# GTwoShield4PATCH2.net
KiCad netlist of a schematic drawn in EAGLE
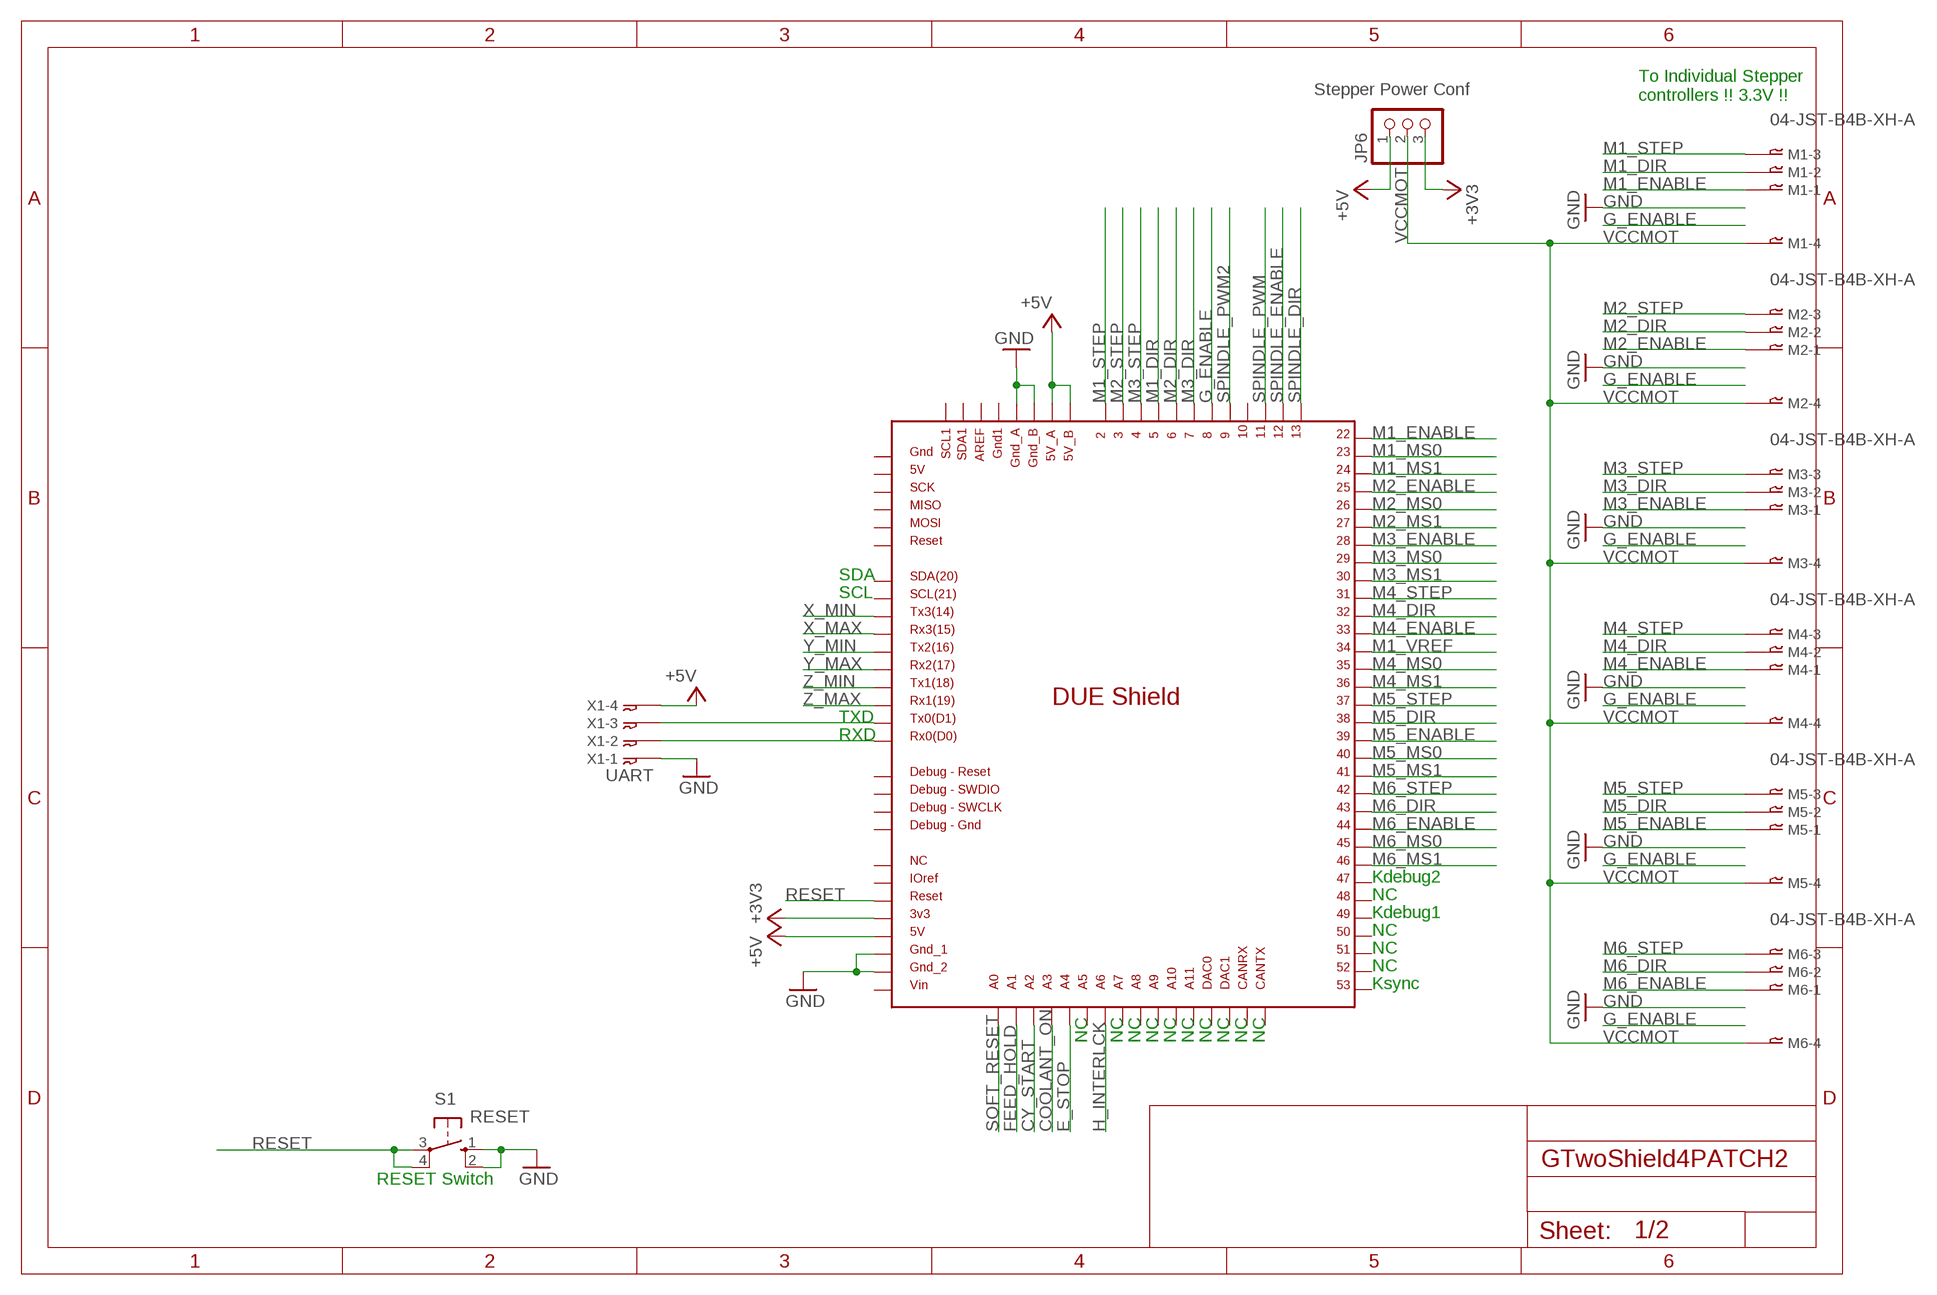
[diagram p0: schematic, sheet 1]
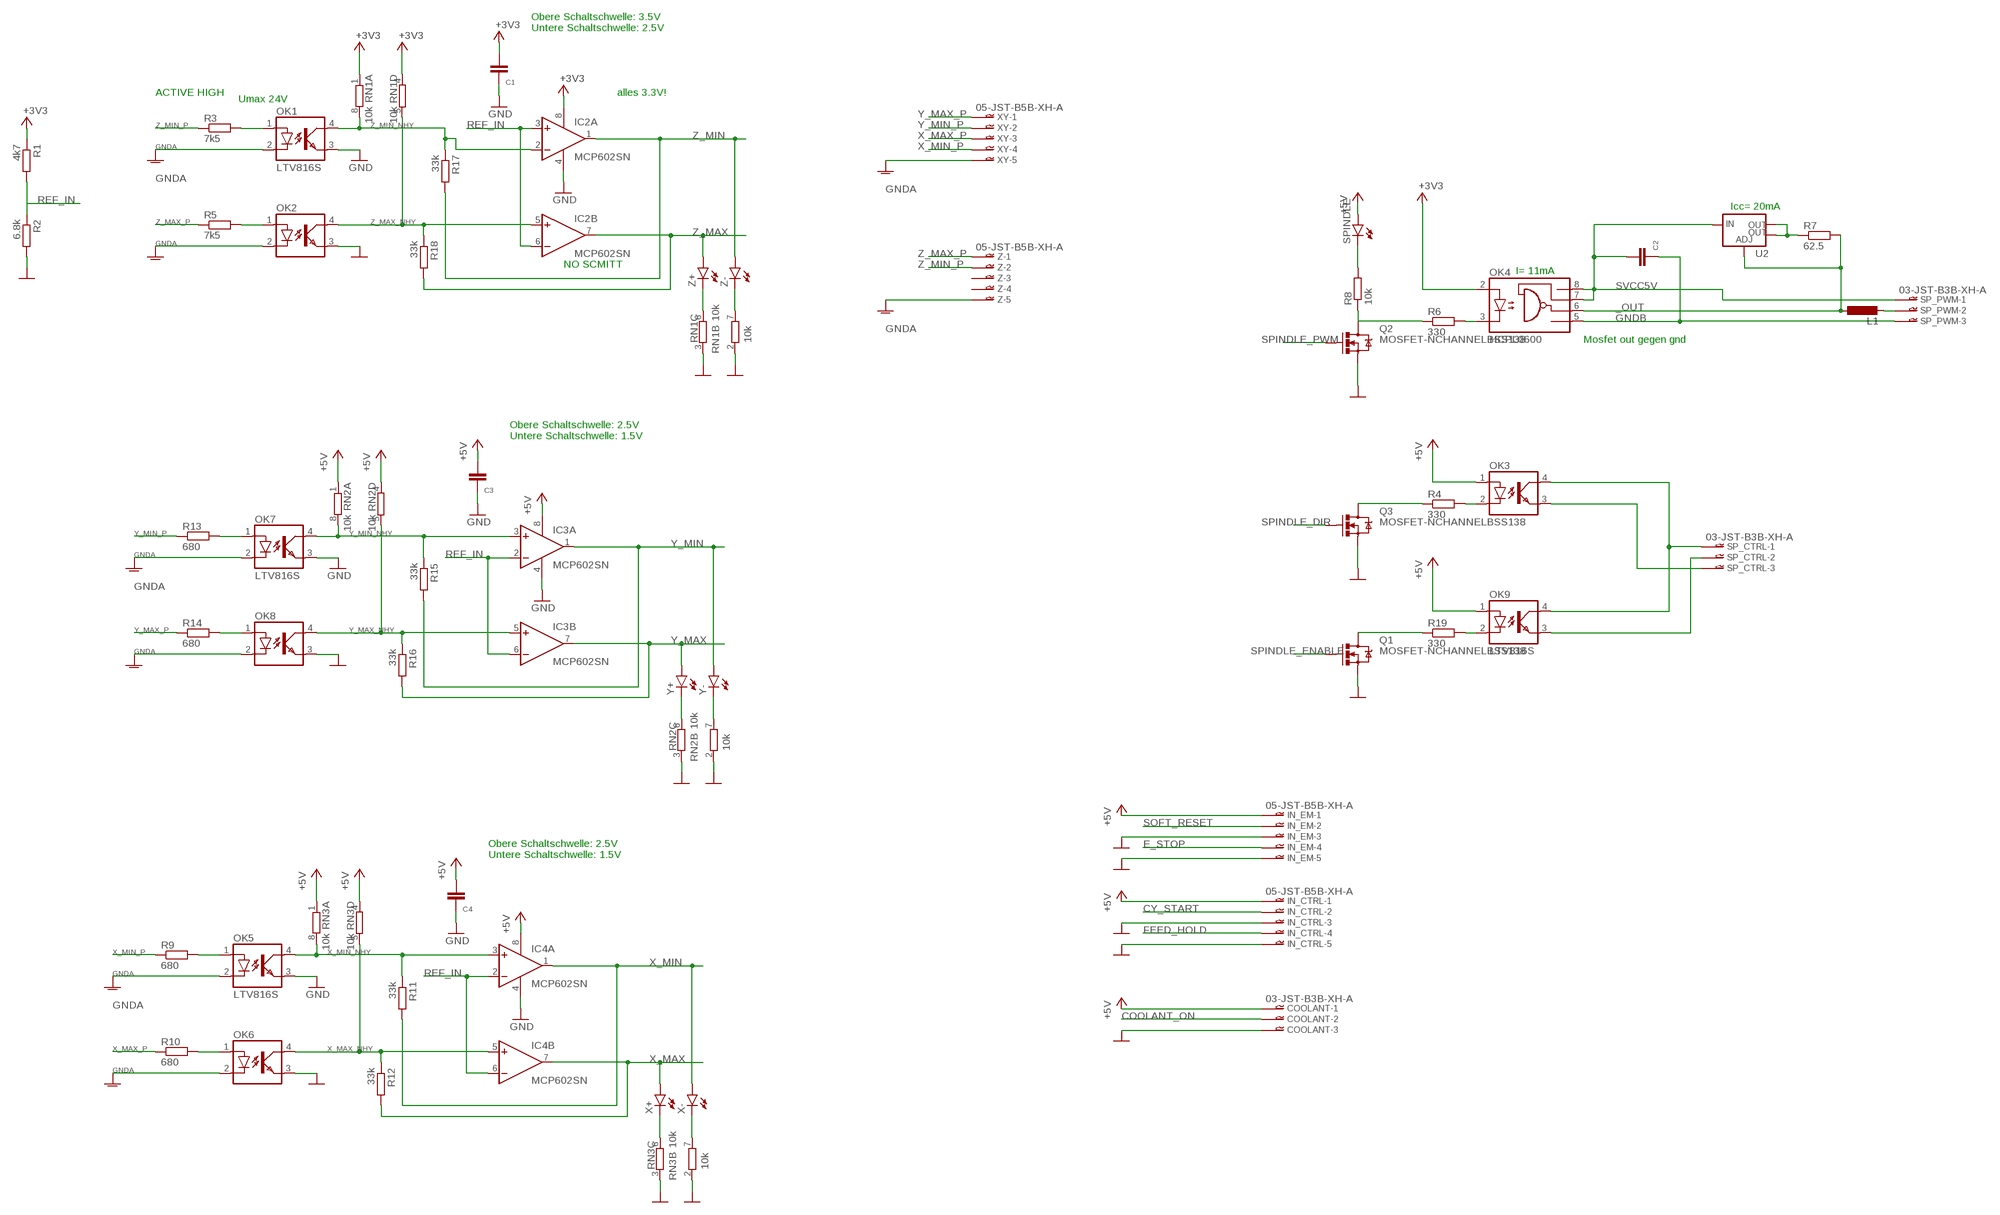
[diagram p1: schematic, sheet 2]

(export (version "E")
  (design (tool "Eeschema 10.0.6"))
  (components
    (comp (ref "C1")
      (value "100nf")
      (footprint "eagle-import:C0603K")
      (libsource (lib "eagle-import") (part "C-EUC0603K"))
    )
    (comp (ref "C2")
      (value "100nf")
      (footprint "eagle-import:C0603K")
      (libsource (lib "eagle-import") (part "C-EUC0603K"))
    )
    (comp (ref "C3")
      (value "100nf")
      (footprint "eagle-import:C0603K")
      (libsource (lib "eagle-import") (part "C-EUC0603K"))
    )
    (comp (ref "C4")
      (value "100nf")
      (footprint "eagle-import:C0603K")
      (libsource (lib "eagle-import") (part "C-EUC0603K"))
    )
    (comp (ref "COOLANT")
      (value "03-JST-B3B-XH-A")
      (footprint "eagle-import:B3B-XH")
      (libsource (lib "eagle-import") (part "03-JST-B3B-XH-A"))
    )
    (comp (ref "IC2")
      (value "MCP602SN")
      (footprint "eagle-import:SO08")
      (libsource (lib "eagle-import") (part "MCP602SN"))
    )
    (comp (ref "IC3")
      (value "MCP602SN")
      (footprint "eagle-import:SO08")
      (libsource (lib "eagle-import") (part "MCP602SN"))
    )
    (comp (ref "IC4")
      (value "MCP602SN")
      (footprint "eagle-import:SO08")
      (libsource (lib "eagle-import") (part "MCP602SN"))
    )
    (comp (ref "IN_CTRL")
      (value "05-JST-B5B-XH-A")
      (footprint "eagle-import:B5B-XH")
      (libsource (lib "eagle-import") (part "05-JST-B5B-XH-A"))
    )
    (comp (ref "IN_EM")
      (value "05-JST-B5B-XH-A")
      (footprint "eagle-import:B5B-XH")
      (libsource (lib "eagle-import") (part "05-JST-B5B-XH-A"))
    )
    (comp (ref "L1")
      (value "L-EU0207/10")
      (footprint "eagle-import:0207_10")
      (libsource (lib "eagle-import") (part "L-EU0207/10"))
    )
    (comp (ref "OK1")
      (value "LTV816S")
      (footprint "eagle-import:DIL4-SMD")
      (fields (field (name "SPICEPREFIX") "O"))
      (libsource (lib "eagle-import") (part "LTV816S"))
    )
    (comp (ref "OK2")
      (value "LTV816S")
      (footprint "eagle-import:DIL4-SMD")
      (fields (field (name "SPICEPREFIX") "O"))
      (libsource (lib "eagle-import") (part "LTV816S"))
    )
    (comp (ref "OK3")
      (value "LTV816S")
      (footprint "eagle-import:DIL4-SMD")
      (fields (field (name "SPICEPREFIX") "O"))
      (libsource (lib "eagle-import") (part "LTV816S"))
    )
    (comp (ref "OK4")
      (value "HCPL0600")
      (footprint "eagle-import:SOIC08")
      (fields (field (name "MF") "AGILENT TECHNOLOGIES") (field (name "MPN") "HCPL-0600-000E"))
      (libsource (lib "eagle-import") (part "HCPL0600"))
    )
    (comp (ref "OK5")
      (value "LTV816S")
      (footprint "eagle-import:DIL4-SMD")
      (fields (field (name "SPICEPREFIX") "O"))
      (libsource (lib "eagle-import") (part "LTV816S"))
    )
    (comp (ref "OK6")
      (value "LTV816S")
      (footprint "eagle-import:DIL4-SMD")
      (fields (field (name "SPICEPREFIX") "O"))
      (libsource (lib "eagle-import") (part "LTV816S"))
    )
    (comp (ref "OK7")
      (value "LTV816S")
      (footprint "eagle-import:DIL4-SMD")
      (fields (field (name "SPICEPREFIX") "O"))
      (libsource (lib "eagle-import") (part "LTV816S"))
    )
    (comp (ref "OK8")
      (value "LTV816S")
      (footprint "eagle-import:DIL4-SMD")
      (fields (field (name "SPICEPREFIX") "O"))
      (libsource (lib "eagle-import") (part "LTV816S"))
    )
    (comp (ref "OK9")
      (value "LTV816S")
      (footprint "eagle-import:DIL4-SMD")
      (fields (field (name "SPICEPREFIX") "O"))
      (libsource (lib "eagle-import") (part "LTV816S"))
    )
    (comp (ref "Q1")
      (value "MOSFET-NCHANNELBSS138")
      (footprint "eagle-import:SOT23")
      (libsource (lib "eagle-import") (part "MOSFET-NCHANNELBSS138"))
    )
    (comp (ref "Q2")
      (value "MOSFET-NCHANNELBSS138")
      (footprint "eagle-import:SOT23")
      (libsource (lib "eagle-import") (part "MOSFET-NCHANNELBSS138"))
    )
    (comp (ref "Q3")
      (value "MOSFET-NCHANNELBSS138")
      (footprint "eagle-import:SOT23")
      (libsource (lib "eagle-import") (part "MOSFET-NCHANNELBSS138"))
    )
    (comp (ref "R1")
      (value "4k7")
      (footprint "eagle-import:R0805")
      (libsource (lib "eagle-import") (part "R-EU_R0805"))
    )
    (comp (ref "R2")
      (value "6.8k")
      (footprint "eagle-import:R0805")
      (libsource (lib "eagle-import") (part "R-EU_R0805"))
    )
    (comp (ref "R3")
      (value "7k5")
      (footprint "eagle-import:R0805")
      (fields (field (name "SPICEPREFIX") "R"))
      (libsource (lib "eagle-import") (part "resistor_348_R-EU_R0805"))
    )
    (comp (ref "R4")
      (value "330")
      (footprint "eagle-import:R0805")
      (fields (field (name "SPICEPREFIX") "R"))
      (libsource (lib "eagle-import") (part "resistor_348_R-EU_R0805"))
    )
    (comp (ref "R5")
      (value "7k5")
      (footprint "eagle-import:R0805")
      (fields (field (name "SPICEPREFIX") "R"))
      (libsource (lib "eagle-import") (part "resistor_348_R-EU_R0805"))
    )
    (comp (ref "R6")
      (value "330")
      (footprint "eagle-import:R0805")
      (fields (field (name "SPICEPREFIX") "R"))
      (libsource (lib "eagle-import") (part "resistor_348_R-EU_R0805"))
    )
    (comp (ref "R7")
      (value "62.5")
      (footprint "eagle-import:R0805")
      (fields (field (name "SPICEPREFIX") "R"))
      (libsource (lib "eagle-import") (part "resistor_348_R-EU_R0805"))
    )
    (comp (ref "R8")
      (value "10k")
      (footprint "eagle-import:R0805")
      (fields (field (name "SPICEPREFIX") "R"))
      (libsource (lib "eagle-import") (part "resistor_348_R-EU_R0805"))
    )
    (comp (ref "R9")
      (value "680")
      (footprint "eagle-import:R0805")
      (fields (field (name "SPICEPREFIX") "R"))
      (libsource (lib "eagle-import") (part "resistor_348_R-EU_R0805"))
    )
    (comp (ref "R10")
      (value "680")
      (footprint "eagle-import:R0805")
      (fields (field (name "SPICEPREFIX") "R"))
      (libsource (lib "eagle-import") (part "resistor_348_R-EU_R0805"))
    )
    (comp (ref "R11")
      (value "33k")
      (footprint "eagle-import:R0805")
      (libsource (lib "eagle-import") (part "R-EU_R0805"))
    )
    (comp (ref "R12")
      (value "33k")
      (footprint "eagle-import:R0805")
      (libsource (lib "eagle-import") (part "R-EU_R0805"))
    )
    (comp (ref "R13")
      (value "680")
      (footprint "eagle-import:R0805")
      (fields (field (name "SPICEPREFIX") "R"))
      (libsource (lib "eagle-import") (part "resistor_348_R-EU_R0805"))
    )
    (comp (ref "R14")
      (value "680")
      (footprint "eagle-import:R0805")
      (fields (field (name "SPICEPREFIX") "R"))
      (libsource (lib "eagle-import") (part "resistor_348_R-EU_R0805"))
    )
    (comp (ref "R15")
      (value "33k")
      (footprint "eagle-import:R0805")
      (libsource (lib "eagle-import") (part "R-EU_R0805"))
    )
    (comp (ref "R16")
      (value "33k")
      (footprint "eagle-import:R0805")
      (libsource (lib "eagle-import") (part "R-EU_R0805"))
    )
    (comp (ref "R17")
      (value "33k")
      (footprint "eagle-import:R0805")
      (libsource (lib "eagle-import") (part "R-EU_R0805"))
    )
    (comp (ref "R18")
      (value "33k")
      (footprint "eagle-import:R0805")
      (libsource (lib "eagle-import") (part "R-EU_R0805"))
    )
    (comp (ref "R19")
      (value "330")
      (footprint "eagle-import:R0805")
      (fields (field (name "SPICEPREFIX") "R"))
      (libsource (lib "eagle-import") (part "resistor_348_R-EU_R0805"))
    )
    (comp (ref "RN1")
      (value "10k")
      (footprint "eagle-import:0603-ARC")
      (libsource (lib "eagle-import") (part "4R-N0603-ARC"))
    )
    (comp (ref "RN2")
      (value "10k")
      (footprint "eagle-import:0603-ARC")
      (libsource (lib "eagle-import") (part "4R-N0603-ARC"))
    )
    (comp (ref "RN3")
      (value "10k")
      (footprint "eagle-import:0603-ARC")
      (libsource (lib "eagle-import") (part "4R-N0603-ARC"))
    )
    (comp (ref "SPINDLE")
      (value "LEDCHIP-LED0805")
      (footprint "eagle-import:CHIP-LED0805")
      (libsource (lib "eagle-import") (part "LEDCHIP-LED0805"))
    )
    (comp (ref "SP_CTRL")
      (value "03-JST-B3B-XH-A")
      (footprint "eagle-import:B3B-XH")
      (libsource (lib "eagle-import") (part "03-JST-B3B-XH-A"))
    )
    (comp (ref "SP_PWM")
      (value "03-JST-B3B-XH-A")
      (footprint "eagle-import:B3B-XH")
      (libsource (lib "eagle-import") (part "03-JST-B3B-XH-A"))
    )
    (comp (ref "U2")
      (value "V_REG_LM1117SOT223")
      (footprint "eagle-import:SOT223")
      (libsource (lib "eagle-import") (part "V_REG_LM1117SOT223"))
    )
    (comp (ref "X+")
      (value "LEDCHIP-LED0805")
      (footprint "eagle-import:CHIP-LED0805")
      (libsource (lib "eagle-import") (part "LEDCHIP-LED0805"))
    )
    (comp (ref "X-")
      (value "LEDCHIP-LED0805")
      (footprint "eagle-import:CHIP-LED0805")
      (libsource (lib "eagle-import") (part "LEDCHIP-LED0805"))
    )
    (comp (ref "XY")
      (value "05-JST-B5B-XH-A")
      (footprint "eagle-import:B5B-XH")
      (libsource (lib "eagle-import") (part "05-JST-B5B-XH-A"))
    )
    (comp (ref "Y+")
      (value "LEDCHIP-LED0805")
      (footprint "eagle-import:CHIP-LED0805")
      (libsource (lib "eagle-import") (part "LEDCHIP-LED0805"))
    )
    (comp (ref "Y-")
      (value "LEDCHIP-LED0805")
      (footprint "eagle-import:CHIP-LED0805")
      (libsource (lib "eagle-import") (part "LEDCHIP-LED0805"))
    )
    (comp (ref "Z")
      (value "05-JST-B5B-XH-A")
      (footprint "eagle-import:B5B-XH")
      (libsource (lib "eagle-import") (part "05-JST-B5B-XH-A"))
    )
    (comp (ref "Z+")
      (value "LEDCHIP-LED0805")
      (footprint "eagle-import:CHIP-LED0805")
      (libsource (lib "eagle-import") (part "LEDCHIP-LED0805"))
    )
    (comp (ref "Z-")
      (value "LEDCHIP-LED0805")
      (footprint "eagle-import:CHIP-LED0805")
      (libsource (lib "eagle-import") (part "LEDCHIP-LED0805"))
    )
    (comp (ref "JP6")
      (value "Stepper Power Conf")
      (footprint "eagle-import:1X03")
      (libsource (lib "eagle-import") (part "PINHD-1X3"))
    )
    (comp (ref "M1")
      (value "04-JST-B4B-XH-A")
      (footprint "eagle-import:B4B-XH")
      (libsource (lib "eagle-import") (part "04-JST-B4B-XH-A"))
    )
    (comp (ref "M2")
      (value "04-JST-B4B-XH-A")
      (footprint "eagle-import:B4B-XH")
      (libsource (lib "eagle-import") (part "04-JST-B4B-XH-A"))
    )
    (comp (ref "M3")
      (value "04-JST-B4B-XH-A")
      (footprint "eagle-import:B4B-XH")
      (libsource (lib "eagle-import") (part "04-JST-B4B-XH-A"))
    )
    (comp (ref "M4")
      (value "04-JST-B4B-XH-A")
      (footprint "eagle-import:B4B-XH")
      (libsource (lib "eagle-import") (part "04-JST-B4B-XH-A"))
    )
    (comp (ref "M5")
      (value "04-JST-B4B-XH-A")
      (footprint "eagle-import:B4B-XH")
      (libsource (lib "eagle-import") (part "04-JST-B4B-XH-A"))
    )
    (comp (ref "M6")
      (value "04-JST-B4B-XH-A")
      (footprint "eagle-import:B4B-XH")
      (libsource (lib "eagle-import") (part "04-JST-B4B-XH-A"))
    )
    (comp (ref "S1")
      (value "RESET")
      (footprint "eagle-import:B3F-10XX")
      (fields (field (name "MPN") "B3F-1000"))
      (libsource (lib "eagle-import") (part "10-XX"))
    )
    (comp (ref "U$1")
      (value "DUE(NORMAL)")
      (footprint "eagle-import:DUE(NORMAL)")
      (libsource (lib "eagle-import") (part "DUE(NORMAL)"))
    )
    (comp (ref "X1")
      (value "UART")
      (footprint "eagle-import:B4B-XH")
      (libsource (lib "eagle-import") (part "04-JST-B4B-XH-A"))
    )
  )
  (nets
    (net (code "1") (name "+3V3") (class "Default")
      (node (ref "C1") (pin "2") (pinfunction "2_2") (pintype "passive"))
      (node (ref "IC2") (pin "8") (pinfunction "V+_8") (pintype "power_in"))
      (node (ref "JP6") (pin "3") (pinfunction "3_3") (pintype "passive"))
      (node (ref "OK4") (pin "2") (pinfunction "A_2") (pintype "passive"))
      (node (ref "R1") (pin "1") (pinfunction "1_1") (pintype "passive"))
      (node (ref "RN1") (pin "1") (pinfunction "1_1") (pintype "passive"))
      (node (ref "RN1") (pin "4") (pinfunction "1_4") (pintype "passive"))
      (node (ref "U$1") (pin "3V3") (pinfunction "3V3_3V3") (pintype "bidirectional"))
    )
    (net (code "2") (name "+5V") (class "Default")
      (node (ref "C3") (pin "2") (pinfunction "2_2") (pintype "passive"))
      (node (ref "C4") (pin "2") (pinfunction "2_2") (pintype "passive"))
      (node (ref "COOLANT") (pin "P$1") (pinfunction "1_P$1") (pintype "passive"))
      (node (ref "IC3") (pin "8") (pinfunction "V+_8") (pintype "power_in"))
      (node (ref "IC4") (pin "8") (pinfunction "V+_8") (pintype "power_in"))
      (node (ref "IN_CTRL") (pin "P$1") (pinfunction "1_P$1") (pintype "passive"))
      (node (ref "IN_EM") (pin "P$1") (pinfunction "1_P$1") (pintype "passive"))
      (node (ref "JP6") (pin "1") (pinfunction "1_1") (pintype "passive"))
      (node (ref "OK3") (pin "1") (pinfunction "A_1") (pintype "passive"))
      (node (ref "OK9") (pin "1") (pinfunction "A_1") (pintype "passive"))
      (node (ref "RN2") (pin "1") (pinfunction "1_1") (pintype "passive"))
      (node (ref "RN2") (pin "4") (pinfunction "1_4") (pintype "passive"))
      (node (ref "RN3") (pin "1") (pinfunction "1_1") (pintype "passive"))
      (node (ref "RN3") (pin "4") (pinfunction "1_4") (pintype "passive"))
      (node (ref "SPINDLE") (pin "A") (pinfunction "A_A") (pintype "passive"))
      (node (ref "U$1") (pin "5V") (pinfunction "5V_5V") (pintype "bidirectional"))
      (node (ref "U$1") (pin "5V_A") (pinfunction "5V_A_5V_A") (pintype "bidirectional"))
      (node (ref "U$1") (pin "5V_B") (pinfunction "5V_B_5V_B") (pintype "bidirectional"))
      (node (ref "X1") (pin "P$4") (pinfunction "1_P$4") (pintype "passive"))
    )
    (net (code "3") (name "COOLANT_ON") (class "Default")
      (node (ref "COOLANT") (pin "P$2") (pinfunction "1_P$2") (pintype "passive"))
      (node (ref "U$1") (pin "A3") (pinfunction "A3_A3") (pintype "bidirectional"))
    )
    (net (code "4") (name "CY_START") (class "Default")
      (node (ref "IN_CTRL") (pin "P$2") (pinfunction "1_P$2") (pintype "passive"))
      (node (ref "U$1") (pin "A2") (pinfunction "A2_A2") (pintype "bidirectional"))
    )
    (net (code "5") (name "E_STOP") (class "Default")
      (node (ref "IN_EM") (pin "P$4") (pinfunction "1_P$4") (pintype "passive"))
      (node (ref "U$1") (pin "A4") (pinfunction "A4_A4") (pintype "bidirectional"))
    )
    (net (code "6") (name "FEED_HOLD") (class "Default")
      (node (ref "IN_CTRL") (pin "P$4") (pinfunction "1_P$4") (pintype "passive"))
      (node (ref "U$1") (pin "A1") (pinfunction "A1_A1") (pintype "bidirectional"))
    )
    (net (code "7") (name "GND") (class "Default")
      (node (ref "C1") (pin "1") (pinfunction "1_1") (pintype "passive"))
      (node (ref "C3") (pin "1") (pinfunction "1_1") (pintype "passive"))
      (node (ref "C4") (pin "1") (pinfunction "1_1") (pintype "passive"))
      (node (ref "COOLANT") (pin "P$3") (pinfunction "1_P$3") (pintype "passive"))
      (node (ref "IC2") (pin "4") (pinfunction "V-_4") (pintype "power_in"))
      (node (ref "IC3") (pin "4") (pinfunction "V-_4") (pintype "power_in"))
      (node (ref "IC4") (pin "4") (pinfunction "V-_4") (pintype "power_in"))
      (node (ref "IN_CTRL") (pin "P$3") (pinfunction "1_P$3") (pintype "passive"))
      (node (ref "IN_CTRL") (pin "P$5") (pinfunction "1_P$5") (pintype "passive"))
      (node (ref "IN_EM") (pin "P$3") (pinfunction "1_P$3") (pintype "passive"))
      (node (ref "IN_EM") (pin "P$5") (pinfunction "1_P$5") (pintype "passive"))
      (node (ref "OK1") (pin "3") (pinfunction "EMIT_3") (pintype "passive"))
      (node (ref "OK2") (pin "3") (pinfunction "EMIT_3") (pintype "passive"))
      (node (ref "OK5") (pin "3") (pinfunction "EMIT_3") (pintype "passive"))
      (node (ref "OK6") (pin "3") (pinfunction "EMIT_3") (pintype "passive"))
      (node (ref "OK7") (pin "3") (pinfunction "EMIT_3") (pintype "passive"))
      (node (ref "OK8") (pin "3") (pinfunction "EMIT_3") (pintype "passive"))
      (node (ref "Q1") (pin "2") (pinfunction "S_2") (pintype "passive"))
      (node (ref "Q2") (pin "2") (pinfunction "S_2") (pintype "passive"))
      (node (ref "Q3") (pin "2") (pinfunction "S_2") (pintype "passive"))
      (node (ref "R2") (pin "2") (pinfunction "2_2") (pintype "passive"))
      (node (ref "RN1") (pin "2") (pinfunction "1_2") (pintype "passive"))
      (node (ref "RN1") (pin "3") (pinfunction "1_3") (pintype "passive"))
      (node (ref "RN2") (pin "2") (pinfunction "1_2") (pintype "passive"))
      (node (ref "RN2") (pin "3") (pinfunction "1_3") (pintype "passive"))
      (node (ref "RN3") (pin "2") (pinfunction "1_2") (pintype "passive"))
      (node (ref "RN3") (pin "3") (pinfunction "1_3") (pintype "passive"))
      (node (ref "S1") (pin "1") (pinfunction "S_1") (pintype "passive"))
      (node (ref "S1") (pin "2") (pinfunction "S1_2") (pintype "passive"))
      (node (ref "U$1") (pin "GND_1") (pinfunction "GND_1_GND_1") (pintype "bidirectional"))
      (node (ref "U$1") (pin "GND_2") (pinfunction "GND_2_GND_2") (pintype "bidirectional"))
      (node (ref "U$1") (pin "GND_A") (pinfunction "GND_A_GND_A") (pintype "bidirectional"))
      (node (ref "U$1") (pin "GND_B") (pinfunction "GND_B_GND_B") (pintype "bidirectional"))
      (node (ref "X1") (pin "P$1") (pinfunction "1_P$1") (pintype "passive"))
    )
    (net (code "8") (name "GNDA") (class "Default")
      (node (ref "OK1") (pin "2") (pinfunction "C_2") (pintype "passive"))
      (node (ref "OK2") (pin "2") (pinfunction "C_2") (pintype "passive"))
      (node (ref "OK5") (pin "2") (pinfunction "C_2") (pintype "passive"))
      (node (ref "OK6") (pin "2") (pinfunction "C_2") (pintype "passive"))
      (node (ref "OK7") (pin "2") (pinfunction "C_2") (pintype "passive"))
      (node (ref "OK8") (pin "2") (pinfunction "C_2") (pintype "passive"))
      (node (ref "XY") (pin "P$5") (pinfunction "1_P$5") (pintype "passive"))
      (node (ref "Z") (pin "P$5") (pinfunction "1_P$5") (pintype "passive"))
    )
    (net (code "9") (name "GNDB") (class "Default")
      (node (ref "C2") (pin "1") (pinfunction "1_1") (pintype "passive"))
      (node (ref "OK4") (pin "5") (pinfunction "GND_5") (pintype "passive"))
      (node (ref "SP_PWM") (pin "P$3") (pinfunction "1_P$3") (pintype "passive"))
    )
    (net (code "10") (name "G_ENABLE") (class "Default")
      (node (ref "U$1") (pin "8") (pinfunction "8_8") (pintype "bidirectional"))
    )
    (net (code "11") (name "H_INTERLCK") (class "Default")
      (node (ref "U$1") (pin "A6") (pinfunction "A6_A6") (pintype "bidirectional"))
    )
    (net (code "12") (name "M1_DIR") (class "Default")
      (node (ref "M1") (pin "P$2") (pinfunction "1_P$2") (pintype "passive"))
      (node (ref "U$1") (pin "5") (pinfunction "5_5") (pintype "bidirectional"))
    )
    (net (code "13") (name "M1_ENABLE") (class "Default")
      (node (ref "M1") (pin "P$1") (pinfunction "1_P$1") (pintype "passive"))
      (node (ref "U$1") (pin "22") (pinfunction "22_22") (pintype "bidirectional"))
    )
    (net (code "14") (name "M1_MS0") (class "Default")
      (node (ref "U$1") (pin "23") (pinfunction "23_23") (pintype "bidirectional"))
    )
    (net (code "15") (name "M1_MS1") (class "Default")
      (node (ref "U$1") (pin "24") (pinfunction "24_24") (pintype "bidirectional"))
    )
    (net (code "16") (name "M1_STEP") (class "Default")
      (node (ref "M1") (pin "P$3") (pinfunction "1_P$3") (pintype "passive"))
      (node (ref "U$1") (pin "2") (pinfunction "2_2") (pintype "bidirectional"))
    )
    (net (code "17") (name "M1_VREF") (class "Default")
      (node (ref "U$1") (pin "34") (pinfunction "34_34") (pintype "bidirectional"))
    )
    (net (code "18") (name "M2_DIR") (class "Default")
      (node (ref "M2") (pin "P$2") (pinfunction "1_P$2") (pintype "passive"))
      (node (ref "U$1") (pin "6") (pinfunction "6_6") (pintype "bidirectional"))
    )
    (net (code "19") (name "M2_ENABLE") (class "Default")
      (node (ref "M2") (pin "P$1") (pinfunction "1_P$1") (pintype "passive"))
      (node (ref "U$1") (pin "25") (pinfunction "25_25") (pintype "bidirectional"))
    )
    (net (code "20") (name "M2_MS0") (class "Default")
      (node (ref "U$1") (pin "26") (pinfunction "26_26") (pintype "bidirectional"))
    )
    (net (code "21") (name "M2_MS1") (class "Default")
      (node (ref "U$1") (pin "27") (pinfunction "27_27") (pintype "bidirectional"))
    )
    (net (code "22") (name "M2_STEP") (class "Default")
      (node (ref "M2") (pin "P$3") (pinfunction "1_P$3") (pintype "passive"))
      (node (ref "U$1") (pin "3") (pinfunction "3_3") (pintype "bidirectional"))
    )
    (net (code "23") (name "M3_DIR") (class "Default")
      (node (ref "M3") (pin "P$2") (pinfunction "1_P$2") (pintype "passive"))
      (node (ref "U$1") (pin "7") (pinfunction "7_7") (pintype "bidirectional"))
    )
    (net (code "24") (name "M3_ENABLE") (class "Default")
      (node (ref "M3") (pin "P$1") (pinfunction "1_P$1") (pintype "passive"))
      (node (ref "U$1") (pin "28") (pinfunction "28_28") (pintype "bidirectional"))
    )
    (net (code "25") (name "M3_MS0") (class "Default")
      (node (ref "U$1") (pin "29") (pinfunction "29_29") (pintype "bidirectional"))
    )
    (net (code "26") (name "M3_MS1") (class "Default")
      (node (ref "U$1") (pin "30") (pinfunction "30_30") (pintype "bidirectional"))
    )
    (net (code "27") (name "M3_STEP") (class "Default")
      (node (ref "M3") (pin "P$3") (pinfunction "1_P$3") (pintype "passive"))
      (node (ref "U$1") (pin "4") (pinfunction "4_4") (pintype "bidirectional"))
    )
    (net (code "28") (name "M4_DIR") (class "Default")
      (node (ref "M4") (pin "P$2") (pinfunction "1_P$2") (pintype "passive"))
      (node (ref "U$1") (pin "32") (pinfunction "32_32") (pintype "bidirectional"))
    )
    (net (code "29") (name "M4_ENABLE") (class "Default")
      (node (ref "M4") (pin "P$1") (pinfunction "1_P$1") (pintype "passive"))
      (node (ref "U$1") (pin "33") (pinfunction "33_33") (pintype "bidirectional"))
    )
    (net (code "30") (name "M4_MS0") (class "Default")
      (node (ref "U$1") (pin "35") (pinfunction "35_35") (pintype "bidirectional"))
    )
    (net (code "31") (name "M4_MS1") (class "Default")
      (node (ref "U$1") (pin "36") (pinfunction "36_36") (pintype "bidirectional"))
    )
    (net (code "32") (name "M4_STEP") (class "Default")
      (node (ref "M4") (pin "P$3") (pinfunction "1_P$3") (pintype "passive"))
      (node (ref "U$1") (pin "31") (pinfunction "31_31") (pintype "bidirectional"))
    )
    (net (code "33") (name "M5_DIR") (class "Default")
      (node (ref "M5") (pin "P$2") (pinfunction "1_P$2") (pintype "passive"))
      (node (ref "U$1") (pin "38") (pinfunction "38_38") (pintype "bidirectional"))
    )
    (net (code "34") (name "M5_ENABLE") (class "Default")
      (node (ref "M5") (pin "P$1") (pinfunction "1_P$1") (pintype "passive"))
      (node (ref "U$1") (pin "39") (pinfunction "39_39") (pintype "bidirectional"))
    )
    (net (code "35") (name "M5_MS0") (class "Default")
      (node (ref "U$1") (pin "40") (pinfunction "40_40") (pintype "bidirectional"))
    )
    (net (code "36") (name "M5_MS1") (class "Default")
      (node (ref "U$1") (pin "41") (pinfunction "41_41") (pintype "bidirectional"))
    )
    (net (code "37") (name "M5_STEP") (class "Default")
      (node (ref "M5") (pin "P$3") (pinfunction "1_P$3") (pintype "passive"))
      (node (ref "U$1") (pin "37") (pinfunction "37_37") (pintype "bidirectional"))
    )
    (net (code "38") (name "M6_DIR") (class "Default")
      (node (ref "M6") (pin "P$2") (pinfunction "1_P$2") (pintype "passive"))
      (node (ref "U$1") (pin "43") (pinfunction "43_43") (pintype "bidirectional"))
    )
    (net (code "39") (name "M6_ENABLE") (class "Default")
      (node (ref "M6") (pin "P$1") (pinfunction "1_P$1") (pintype "passive"))
      (node (ref "U$1") (pin "44") (pinfunction "44_44") (pintype "bidirectional"))
    )
    (net (code "40") (name "M6_MS0") (class "Default")
      (node (ref "U$1") (pin "45") (pinfunction "45_45") (pintype "bidirectional"))
    )
    (net (code "41") (name "M6_MS1") (class "Default")
      (node (ref "U$1") (pin "46") (pinfunction "46_46") (pintype "bidirectional"))
    )
    (net (code "42") (name "M6_STEP") (class "Default")
      (node (ref "M6") (pin "P$3") (pinfunction "1_P$3") (pintype "passive"))
      (node (ref "U$1") (pin "42") (pinfunction "42_42") (pintype "bidirectional"))
    )
    (net (code "43") (name "Net-(OK1-A)") (class "Default")
      (node (ref "OK1") (pin "1") (pinfunction "A_1") (pintype "passive"))
      (node (ref "R3") (pin "2") (pinfunction "2_2") (pintype "passive"))
    )
    (net (code "44") (name "Net-(OK2-A)") (class "Default")
      (node (ref "OK2") (pin "1") (pinfunction "A_1") (pintype "passive"))
      (node (ref "R5") (pin "2") (pinfunction "2_2") (pintype "passive"))
    )
    (net (code "45") (name "Net-(OK3-C)") (class "Default")
      (node (ref "OK3") (pin "2") (pinfunction "C_2") (pintype "passive"))
      (node (ref "R4") (pin "2") (pinfunction "2_2") (pintype "passive"))
    )
    (net (code "46") (name "Net-(OK3-COL)") (class "Default")
      (node (ref "OK3") (pin "4") (pinfunction "COL_4") (pintype "passive"))
      (node (ref "OK9") (pin "4") (pinfunction "COL_4") (pintype "passive"))
      (node (ref "SP_CTRL") (pin "P$1") (pinfunction "1_P$1") (pintype "passive"))
    )
    (net (code "47") (name "Net-(OK3-EMIT)") (class "Default")
      (node (ref "OK3") (pin "3") (pinfunction "EMIT_3") (pintype "passive"))
      (node (ref "SP_CTRL") (pin "P$3") (pinfunction "1_P$3") (pintype "passive"))
    )
    (net (code "48") (name "Net-(OK4-C)") (class "Default")
      (node (ref "OK4") (pin "3") (pinfunction "C_3") (pintype "passive"))
      (node (ref "R6") (pin "2") (pinfunction "2_2") (pintype "passive"))
    )
    (net (code "49") (name "Net-(OK5-A)") (class "Default")
      (node (ref "OK5") (pin "1") (pinfunction "A_1") (pintype "passive"))
      (node (ref "R9") (pin "2") (pinfunction "2_2") (pintype "passive"))
    )
    (net (code "50") (name "Net-(OK6-A)") (class "Default")
      (node (ref "OK6") (pin "1") (pinfunction "A_1") (pintype "passive"))
      (node (ref "R10") (pin "2") (pinfunction "2_2") (pintype "passive"))
    )
    (net (code "51") (name "Net-(OK7-A)") (class "Default")
      (node (ref "OK7") (pin "1") (pinfunction "A_1") (pintype "passive"))
      (node (ref "R13") (pin "2") (pinfunction "2_2") (pintype "passive"))
    )
    (net (code "52") (name "Net-(OK8-A)") (class "Default")
      (node (ref "OK8") (pin "1") (pinfunction "A_1") (pintype "passive"))
      (node (ref "R14") (pin "2") (pinfunction "2_2") (pintype "passive"))
    )
    (net (code "53") (name "Net-(OK9-C)") (class "Default")
      (node (ref "OK9") (pin "2") (pinfunction "C_2") (pintype "passive"))
      (node (ref "R19") (pin "2") (pinfunction "2_2") (pintype "passive"))
    )
    (net (code "54") (name "Net-(OK9-EMIT)") (class "Default")
      (node (ref "OK9") (pin "3") (pinfunction "EMIT_3") (pintype "passive"))
      (node (ref "SP_CTRL") (pin "P$2") (pinfunction "1_P$2") (pintype "passive"))
    )
    (net (code "55") (name "Net-(Q1-D)") (class "Default")
      (node (ref "Q1") (pin "3") (pinfunction "D_3") (pintype "passive"))
      (node (ref "R19") (pin "1") (pinfunction "1_1") (pintype "passive"))
    )
    (net (code "56") (name "Net-(Q2-D)") (class "Default")
      (node (ref "Q2") (pin "3") (pinfunction "D_3") (pintype "passive"))
      (node (ref "R6") (pin "1") (pinfunction "1_1") (pintype "passive"))
      (node (ref "R8") (pin "1") (pinfunction "1_1") (pintype "passive"))
    )
    (net (code "57") (name "Net-(Q3-D)") (class "Default")
      (node (ref "Q3") (pin "3") (pinfunction "D_3") (pintype "passive"))
      (node (ref "R4") (pin "1") (pinfunction "1_1") (pintype "passive"))
    )
    (net (code "58") (name "Net-(R7-Pad1)") (class "Default")
      (node (ref "R7") (pin "1") (pinfunction "1_1") (pintype "passive"))
      (node (ref "U2") (pin "2") (pinfunction "OUT_2") (pintype "output"))
      (node (ref "U2") (pin "4") (pinfunction "OUT_4") (pintype "output"))
    )
    (net (code "59") (name "Net-(R8-Pad2)") (class "Default")
      (node (ref "R8") (pin "2") (pinfunction "2_2") (pintype "passive"))
      (node (ref "SPINDLE") (pin "C") (pinfunction "C_C") (pintype "passive"))
    )
    (net (code "60") (name "Net-(RN1B-2)") (class "Default")
      (node (ref "RN1") (pin "7") (pinfunction "2_7") (pintype "passive"))
      (node (ref "Z-") (pin "C") (pinfunction "C_C") (pintype "passive"))
    )
    (net (code "61") (name "Net-(RN1C-2)") (class "Default")
      (node (ref "RN1") (pin "6") (pinfunction "2_6") (pintype "passive"))
      (node (ref "Z+") (pin "C") (pinfunction "C_C") (pintype "passive"))
    )
    (net (code "62") (name "Net-(RN2B-2)") (class "Default")
      (node (ref "RN2") (pin "7") (pinfunction "2_7") (pintype "passive"))
      (node (ref "Y-") (pin "C") (pinfunction "C_C") (pintype "passive"))
    )
    (net (code "63") (name "Net-(RN2C-2)") (class "Default")
      (node (ref "RN2") (pin "6") (pinfunction "2_6") (pintype "passive"))
      (node (ref "Y+") (pin "C") (pinfunction "C_C") (pintype "passive"))
    )
    (net (code "64") (name "Net-(RN3B-2)") (class "Default")
      (node (ref "RN3") (pin "7") (pinfunction "2_7") (pintype "passive"))
      (node (ref "X-") (pin "C") (pinfunction "C_C") (pintype "passive"))
    )
    (net (code "65") (name "Net-(RN3C-2)") (class "Default")
      (node (ref "RN3") (pin "6") (pinfunction "2_6") (pintype "passive"))
      (node (ref "X+") (pin "C") (pinfunction "C_C") (pintype "passive"))
    )
    (net (code "66") (name "Net-(SP_PWMB-1)") (class "Default")
      (node (ref "L1") (pin "2") (pinfunction "2_2") (pintype "passive"))
      (node (ref "SP_PWM") (pin "P$2") (pinfunction "1_P$2") (pintype "passive"))
    )
    (net (code "67") (name "Net-(X1B-1)") (class "Default")
      (node (ref "U$1") (pin "RX0") (pinfunction "RX0_RX0") (pintype "bidirectional"))
      (node (ref "X1") (pin "P$2") (pinfunction "1_P$2") (pintype "passive"))
    )
    (net (code "68") (name "Net-(X1C-1)") (class "Default")
      (node (ref "U$1") (pin "TX0") (pinfunction "TX0_TX0") (pintype "bidirectional"))
      (node (ref "X1") (pin "P$3") (pinfunction "1_P$3") (pintype "passive"))
    )
    (net (code "69") (name "REF_IN") (class "Default")
      (node (ref "IC2") (pin "3") (pinfunction "+IN_3") (pintype "input"))
      (node (ref "IC2") (pin "6") (pinfunction "-IN_6") (pintype "input"))
      (node (ref "IC3") (pin "2") (pinfunction "-IN_2") (pintype "input"))
      (node (ref "IC3") (pin "6") (pinfunction "-IN_6") (pintype "input"))
      (node (ref "IC4") (pin "2") (pinfunction "-IN_2") (pintype "input"))
      (node (ref "IC4") (pin "6") (pinfunction "-IN_6") (pintype "input"))
      (node (ref "R1") (pin "2") (pinfunction "2_2") (pintype "passive"))
      (node (ref "R2") (pin "1") (pinfunction "1_1") (pintype "passive"))
    )
    (net (code "70") (name "RESET") (class "Default")
      (node (ref "S1") (pin "3") (pinfunction "P_3") (pintype "passive"))
      (node (ref "S1") (pin "4") (pinfunction "P1_4") (pintype "passive"))
      (node (ref "U$1") (pin "RESET") (pinfunction "RESET_RESET") (pintype "bidirectional"))
    )
    (net (code "71") (name "SOFT_RESET") (class "Default")
      (node (ref "IN_EM") (pin "P$2") (pinfunction "1_P$2") (pintype "passive"))
      (node (ref "U$1") (pin "A0") (pinfunction "A0_A0") (pintype "bidirectional"))
    )
    (net (code "72") (name "SPINDLE_DIR") (class "Default")
      (node (ref "Q3") (pin "1") (pinfunction "G_1") (pintype "passive"))
      (node (ref "U$1") (pin "13") (pinfunction "13_13") (pintype "bidirectional"))
    )
    (net (code "73") (name "SPINDLE_ENABLE") (class "Default")
      (node (ref "Q1") (pin "1") (pinfunction "G_1") (pintype "passive"))
      (node (ref "U$1") (pin "12") (pinfunction "12_12") (pintype "bidirectional"))
    )
    (net (code "74") (name "SPINDLE_PWM") (class "Default")
      (node (ref "Q2") (pin "1") (pinfunction "G_1") (pintype "passive"))
      (node (ref "U$1") (pin "11") (pinfunction "11_11") (pintype "bidirectional"))
    )
    (net (code "75") (name "SPINDLE_PWM2") (class "Default")
      (node (ref "U$1") (pin "9") (pinfunction "9_9") (pintype "bidirectional"))
    )
    (net (code "76") (name "SVCC5V") (class "Default")
      (node (ref "C2") (pin "2") (pinfunction "2_2") (pintype "passive"))
      (node (ref "OK4") (pin "7") (pinfunction "VE_7") (pintype "passive"))
      (node (ref "OK4") (pin "8") (pinfunction "VCC_8") (pintype "passive"))
      (node (ref "SP_PWM") (pin "P$1") (pinfunction "1_P$1") (pintype "passive"))
      (node (ref "U2") (pin "3") (pinfunction "IN_3") (pintype "input"))
    )
    (net (code "77") (name "VCCMOT") (class "Default")
      (node (ref "JP6") (pin "2") (pinfunction "2_2") (pintype "passive"))
      (node (ref "M1") (pin "P$4") (pinfunction "1_P$4") (pintype "passive"))
      (node (ref "M2") (pin "P$4") (pinfunction "1_P$4") (pintype "passive"))
      (node (ref "M3") (pin "P$4") (pinfunction "1_P$4") (pintype "passive"))
      (node (ref "M4") (pin "P$4") (pinfunction "1_P$4") (pintype "passive"))
      (node (ref "M5") (pin "P$4") (pinfunction "1_P$4") (pintype "passive"))
      (node (ref "M6") (pin "P$4") (pinfunction "1_P$4") (pintype "passive"))
    )
    (net (code "78") (name "X_MAX") (class "Default")
      (node (ref "IC4") (pin "7") (pinfunction "OUT_7") (pintype "output"))
      (node (ref "R12") (pin "2") (pinfunction "2_2") (pintype "passive"))
      (node (ref "U$1") (pin "RX3") (pinfunction "RX3_RX3") (pintype "bidirectional"))
      (node (ref "X+") (pin "A") (pinfunction "A_A") (pintype "passive"))
    )
    (net (code "79") (name "X_MAX_NHY") (class "Default")
      (node (ref "IC4") (pin "5") (pinfunction "+IN_5") (pintype "input"))
      (node (ref "OK6") (pin "4") (pinfunction "COL_4") (pintype "passive"))
      (node (ref "R12") (pin "1") (pinfunction "1_1") (pintype "passive"))
      (node (ref "RN3") (pin "5") (pinfunction "2_5") (pintype "passive"))
    )
    (net (code "80") (name "X_MAX_P") (class "Default")
      (node (ref "R10") (pin "1") (pinfunction "1_1") (pintype "passive"))
      (node (ref "XY") (pin "P$3") (pinfunction "1_P$3") (pintype "passive"))
    )
    (net (code "81") (name "X_MIN") (class "Default")
      (node (ref "IC4") (pin "1") (pinfunction "OUT_1") (pintype "output"))
      (node (ref "R11") (pin "2") (pinfunction "2_2") (pintype "passive"))
      (node (ref "U$1") (pin "TX3") (pinfunction "TX3_TX3") (pintype "bidirectional"))
      (node (ref "X-") (pin "A") (pinfunction "A_A") (pintype "passive"))
    )
    (net (code "82") (name "X_MIN_NHY") (class "Default")
      (node (ref "IC4") (pin "3") (pinfunction "+IN_3") (pintype "input"))
      (node (ref "OK5") (pin "4") (pinfunction "COL_4") (pintype "passive"))
      (node (ref "R11") (pin "1") (pinfunction "1_1") (pintype "passive"))
      (node (ref "RN3") (pin "8") (pinfunction "2_8") (pintype "passive"))
    )
    (net (code "83") (name "X_MIN_P") (class "Default")
      (node (ref "R9") (pin "1") (pinfunction "1_1") (pintype "passive"))
      (node (ref "XY") (pin "P$4") (pinfunction "1_P$4") (pintype "passive"))
    )
    (net (code "84") (name "Y_MAX") (class "Default")
      (node (ref "IC3") (pin "7") (pinfunction "OUT_7") (pintype "output"))
      (node (ref "R16") (pin "2") (pinfunction "2_2") (pintype "passive"))
      (node (ref "U$1") (pin "RX2") (pinfunction "RX2_RX2") (pintype "bidirectional"))
      (node (ref "Y+") (pin "A") (pinfunction "A_A") (pintype "passive"))
    )
    (net (code "85") (name "Y_MAX_NHY") (class "Default")
      (node (ref "IC3") (pin "5") (pinfunction "+IN_5") (pintype "input"))
      (node (ref "OK8") (pin "4") (pinfunction "COL_4") (pintype "passive"))
      (node (ref "R16") (pin "1") (pinfunction "1_1") (pintype "passive"))
      (node (ref "RN2") (pin "5") (pinfunction "2_5") (pintype "passive"))
    )
    (net (code "86") (name "Y_MAX_P") (class "Default")
      (node (ref "R14") (pin "1") (pinfunction "1_1") (pintype "passive"))
      (node (ref "XY") (pin "P$1") (pinfunction "1_P$1") (pintype "passive"))
    )
    (net (code "87") (name "Y_MIN") (class "Default")
      (node (ref "IC3") (pin "1") (pinfunction "OUT_1") (pintype "output"))
      (node (ref "R15") (pin "2") (pinfunction "2_2") (pintype "passive"))
      (node (ref "U$1") (pin "TX2") (pinfunction "TX2_TX2") (pintype "bidirectional"))
      (node (ref "Y-") (pin "A") (pinfunction "A_A") (pintype "passive"))
    )
    (net (code "88") (name "Y_MIN_NHY") (class "Default")
      (node (ref "IC3") (pin "3") (pinfunction "+IN_3") (pintype "input"))
      (node (ref "OK7") (pin "4") (pinfunction "COL_4") (pintype "passive"))
      (node (ref "R15") (pin "1") (pinfunction "1_1") (pintype "passive"))
      (node (ref "RN2") (pin "8") (pinfunction "2_8") (pintype "passive"))
    )
    (net (code "89") (name "Y_MIN_P") (class "Default")
      (node (ref "R13") (pin "1") (pinfunction "1_1") (pintype "passive"))
      (node (ref "XY") (pin "P$2") (pinfunction "1_P$2") (pintype "passive"))
    )
    (net (code "90") (name "Z_MAX") (class "Default")
      (node (ref "IC2") (pin "7") (pinfunction "OUT_7") (pintype "output"))
      (node (ref "R18") (pin "2") (pinfunction "2_2") (pintype "passive"))
      (node (ref "U$1") (pin "RX1") (pinfunction "RX1_RX1") (pintype "bidirectional"))
      (node (ref "Z+") (pin "A") (pinfunction "A_A") (pintype "passive"))
    )
    (net (code "91") (name "Z_MAX_NHY") (class "Default")
      (node (ref "IC2") (pin "5") (pinfunction "+IN_5") (pintype "input"))
      (node (ref "OK2") (pin "4") (pinfunction "COL_4") (pintype "passive"))
      (node (ref "R18") (pin "1") (pinfunction "1_1") (pintype "passive"))
      (node (ref "RN1") (pin "5") (pinfunction "2_5") (pintype "passive"))
    )
    (net (code "92") (name "Z_MAX_P") (class "Default")
      (node (ref "R5") (pin "1") (pinfunction "1_1") (pintype "passive"))
      (node (ref "Z") (pin "P$1") (pinfunction "1_P$1") (pintype "passive"))
    )
    (net (code "93") (name "Z_MIN") (class "Default")
      (node (ref "IC2") (pin "1") (pinfunction "OUT_1") (pintype "output"))
      (node (ref "R17") (pin "2") (pinfunction "2_2") (pintype "passive"))
      (node (ref "U$1") (pin "TX1") (pinfunction "TX1_TX1") (pintype "bidirectional"))
      (node (ref "Z-") (pin "A") (pinfunction "A_A") (pintype "passive"))
    )
    (net (code "94") (name "Z_MIN_NHY") (class "Default")
      (node (ref "IC2") (pin "2") (pinfunction "-IN_2") (pintype "input"))
      (node (ref "OK1") (pin "4") (pinfunction "COL_4") (pintype "passive"))
      (node (ref "R17") (pin "1") (pinfunction "1_1") (pintype "passive"))
      (node (ref "RN1") (pin "8") (pinfunction "2_8") (pintype "passive"))
    )
    (net (code "95") (name "Z_MIN_P") (class "Default")
      (node (ref "R3") (pin "1") (pinfunction "1_1") (pintype "passive"))
      (node (ref "Z") (pin "P$2") (pinfunction "1_P$2") (pintype "passive"))
    )
    (net (code "96") (name "_OUT") (class "Default")
      (node (ref "L1") (pin "1") (pinfunction "1_1") (pintype "passive"))
      (node (ref "OK4") (pin "6") (pinfunction "VO_6") (pintype "passive"))
      (node (ref "R7") (pin "2") (pinfunction "2_2") (pintype "passive"))
      (node (ref "U2") (pin "1") (pinfunction "ADJ_1") (pintype "input"))
    )
    (net (code "97") (name "unconnected-(U$1-Pad5V_ICSP)") (class "Default")
      (node (ref "U$1") (pin "5V_ICSP") (pinfunction "5V_ICSP_5V_ICSP") (pintype "bidirectional"))
    )
    (net (code "98") (name "unconnected-(U$1-Pad10)") (class "Default")
      (node (ref "U$1") (pin "10") (pinfunction "10_10") (pintype "bidirectional"))
    )
    (net (code "99") (name "unconnected-(U$1-Pad47)") (class "Default")
      (node (ref "U$1") (pin "47") (pinfunction "47_47") (pintype "bidirectional"))
    )
    (net (code "100") (name "unconnected-(U$1-Pad48)") (class "Default")
      (node (ref "U$1") (pin "48") (pinfunction "48_48") (pintype "bidirectional"))
    )
    (net (code "101") (name "unconnected-(U$1-Pad49)") (class "Default")
      (node (ref "U$1") (pin "49") (pinfunction "49_49") (pintype "bidirectional"))
    )
    (net (code "102") (name "unconnected-(U$1-Pad50)") (class "Default")
      (node (ref "U$1") (pin "50") (pinfunction "50_50") (pintype "bidirectional"))
    )
    (net (code "103") (name "unconnected-(U$1-Pad51)") (class "Default")
      (node (ref "U$1") (pin "51") (pinfunction "51_51") (pintype "bidirectional"))
    )
    (net (code "104") (name "unconnected-(U$1-Pad52)") (class "Default")
      (node (ref "U$1") (pin "52") (pinfunction "52_52") (pintype "bidirectional"))
    )
    (net (code "105") (name "unconnected-(U$1-Pad53)") (class "Default")
      (node (ref "U$1") (pin "53") (pinfunction "53_53") (pintype "bidirectional"))
    )
    (net (code "106") (name "unconnected-(U$1-PadA5)") (class "Default")
      (node (ref "U$1") (pin "A5") (pinfunction "A5_A5") (pintype "bidirectional"))
    )
    (net (code "107") (name "unconnected-(U$1-PadA7)") (class "Default")
      (node (ref "U$1") (pin "A7") (pinfunction "A7_A7") (pintype "bidirectional"))
    )
    (net (code "108") (name "unconnected-(U$1-PadA8)") (class "Default")
      (node (ref "U$1") (pin "A8") (pinfunction "A8_A8") (pintype "bidirectional"))
    )
    (net (code "109") (name "unconnected-(U$1-PadA9)") (class "Default")
      (node (ref "U$1") (pin "A9") (pinfunction "A9_A9") (pintype "bidirectional"))
    )
    (net (code "110") (name "unconnected-(U$1-PadA10)") (class "Default")
      (node (ref "U$1") (pin "A10") (pinfunction "A10_A10") (pintype "bidirectional"))
    )
    (net (code "111") (name "unconnected-(U$1-PadA11)") (class "Default")
      (node (ref "U$1") (pin "A11") (pinfunction "A11_A11") (pintype "bidirectional"))
    )
    (net (code "112") (name "unconnected-(U$1-PadAREF)") (class "Default")
      (node (ref "U$1") (pin "AREF") (pinfunction "AREF_AREF") (pintype "bidirectional"))
    )
    (net (code "113") (name "unconnected-(U$1-PadCANRX)") (class "Default")
      (node (ref "U$1") (pin "CANRX") (pinfunction "CANRX_CANRX") (pintype "bidirectional"))
    )
    (net (code "114") (name "unconnected-(U$1-PadCANTX)") (class "Default")
      (node (ref "U$1") (pin "CANTX") (pinfunction "CANTX_CANTX") (pintype "bidirectional"))
    )
    (net (code "115") (name "unconnected-(U$1-PadDAC0)") (class "Default")
      (node (ref "U$1") (pin "DAC0") (pinfunction "DAC0_DAC0") (pintype "bidirectional"))
    )
    (net (code "116") (name "unconnected-(U$1-PadDAC1)") (class "Default")
      (node (ref "U$1") (pin "DAC1") (pinfunction "DAC1_DAC1") (pintype "bidirectional"))
    )
    (net (code "117") (name "unconnected-(U$1-PadGND1)") (class "Default")
      (node (ref "U$1") (pin "GND1") (pinfunction "GND1_GND1") (pintype "bidirectional"))
    )
    (net (code "118") (name "unconnected-(U$1-PadGND_DEBUG)") (class "Default")
      (node (ref "U$1") (pin "GND_DEBUG") (pinfunction "GND_DEBUG_GND_DEBUG") (pintype "bidirectional"))
    )
    (net (code "119") (name "unconnected-(U$1-PadGND_ICSP)") (class "Default")
      (node (ref "U$1") (pin "GND_ICSP") (pinfunction "GND_ICSP_GND_ICSP") (pintype "bidirectional"))
    )
    (net (code "120") (name "unconnected-(U$1-PadIOREF)") (class "Default")
      (node (ref "U$1") (pin "IOREF") (pinfunction "IOREF_IOREF") (pintype "bidirectional"))
    )
    (net (code "121") (name "unconnected-(U$1-PadMISO_ICSP)") (class "Default")
      (node (ref "U$1") (pin "MISO_ICSP") (pinfunction "MISO_ICSP_MISO_ICSP") (pintype "bidirectional"))
    )
    (net (code "122") (name "unconnected-(U$1-PadMOSI_ICSP)") (class "Default")
      (node (ref "U$1") (pin "MOSI_ICSP") (pinfunction "MOSI_ICSP_MOSI_ICSP") (pintype "bidirectional"))
    )
    (net (code "123") (name "unconnected-(U$1-PadNC)") (class "Default")
      (node (ref "U$1") (pin "NC") (pinfunction "NC_NC") (pintype "bidirectional"))
    )
    (net (code "124") (name "unconnected-(U$1-PadRESET_DEBUG)") (class "Default")
      (node (ref "U$1") (pin "RESET_DEBUG") (pinfunction "RESET_DEBUG_RESET_DEBUG") (pintype "bidirectional"))
    )
    (net (code "125") (name "unconnected-(U$1-PadRESET_ICSP)") (class "Default")
      (node (ref "U$1") (pin "RESET_ICSP") (pinfunction "RESET_ICSP_RESET_ICSP") (pintype "bidirectional"))
    )
    (net (code "126") (name "unconnected-(U$1-PadSCK_ICSP)") (class "Default")
      (node (ref "U$1") (pin "SCK_ICSP") (pinfunction "SCK_ICSP_SCK_ICSP") (pintype "bidirectional"))
    )
    (net (code "127") (name "unconnected-(U$1-PadSCL)") (class "Default")
      (node (ref "U$1") (pin "SCL") (pinfunction "SCL_SCL") (pintype "bidirectional"))
    )
    (net (code "128") (name "unconnected-(U$1-PadSCL1)") (class "Default")
      (node (ref "U$1") (pin "SCL1") (pinfunction "SCL1_SCL1") (pintype "bidirectional"))
    )
    (net (code "129") (name "unconnected-(U$1-PadSDA)") (class "Default")
      (node (ref "U$1") (pin "SDA") (pinfunction "SDA_SDA") (pintype "bidirectional"))
    )
    (net (code "130") (name "unconnected-(U$1-PadSDA1)") (class "Default")
      (node (ref "U$1") (pin "SDA1") (pinfunction "SDA1_SDA1") (pintype "bidirectional"))
    )
    (net (code "131") (name "unconnected-(U$1-PadSWCLK_DEBUG)") (class "Default")
      (node (ref "U$1") (pin "SWCLK_DEBUG") (pinfunction "SWCLK_DEBUG_SWCLK_DEBUG") (pintype "bidirectional"))
    )
    (net (code "132") (name "unconnected-(U$1-PadSWDIO_DEBUG)") (class "Default")
      (node (ref "U$1") (pin "SWDIO_DEBUG") (pinfunction "SWDIO_DEBUG_SWDIO_DEBUG") (pintype "bidirectional"))
    )
    (net (code "133") (name "unconnected-(U$1-PadVIN)") (class "Default")
      (node (ref "U$1") (pin "VIN") (pinfunction "VIN_VIN") (pintype "bidirectional"))
    )
    (net (code "134") (name "unconnected-(ZC-1-PadP$3)") (class "Default")
      (node (ref "Z") (pin "P$3") (pinfunction "1_P$3") (pintype "passive"))
    )
    (net (code "135") (name "unconnected-(ZD-1-PadP$4)") (class "Default")
      (node (ref "Z") (pin "P$4") (pinfunction "1_P$4") (pintype "passive"))
    )
  )
)
